# MIR50_last_version.net
KiCad netlist of a schematic drawn in EAGLE
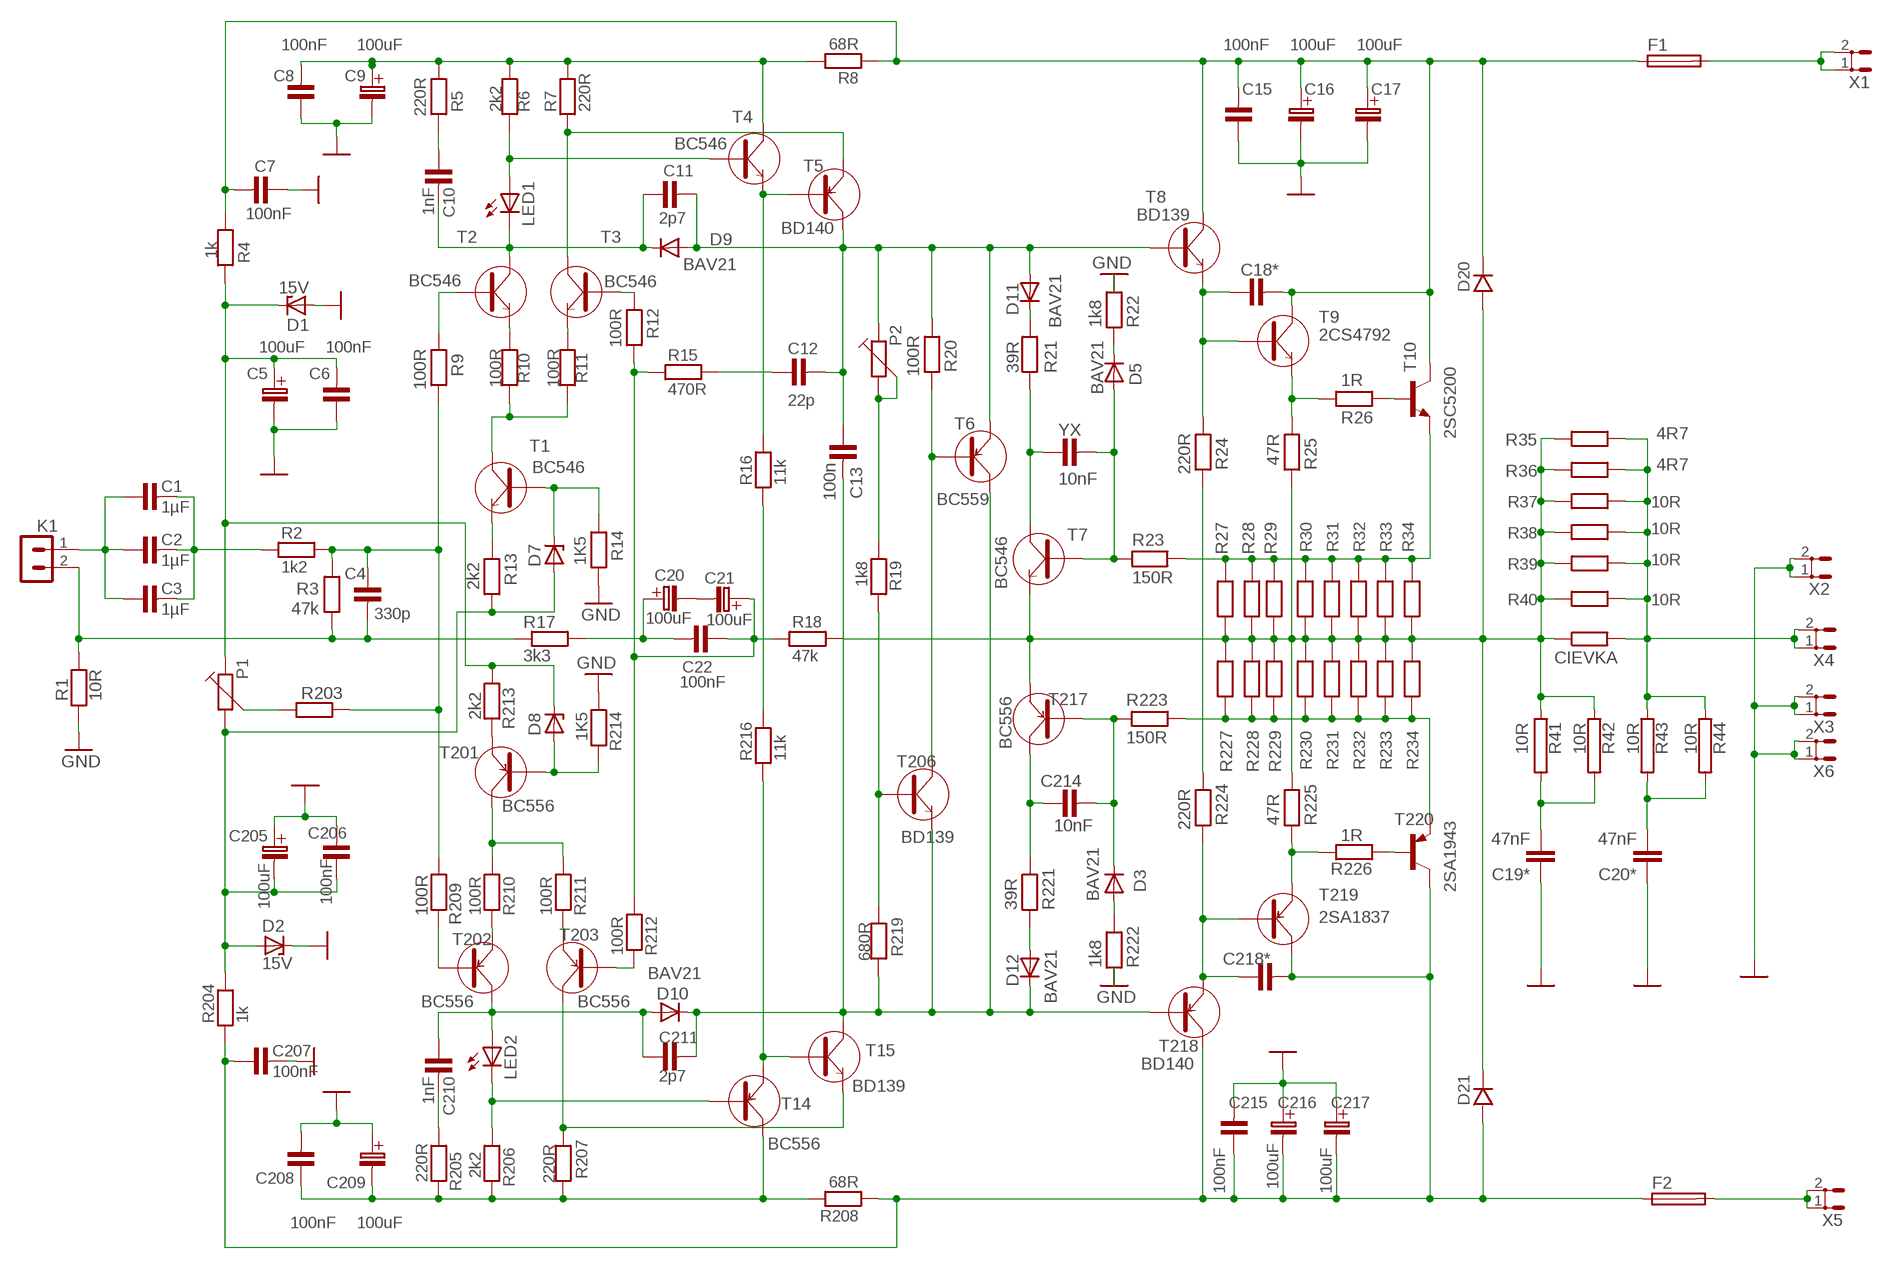
[diagram p0: schematic, sheet 1]

(export (version "E")
  (design (tool "Eeschema 10.0.6"))
  (components
    (comp (ref "C1")
      (value "1µF")
      (footprint "eagle-import:C-5")
      (libsource (lib "eagle-import") (part "C-KERAMIK_5"))
    )
    (comp (ref "C2")
      (value "1µF")
      (footprint "eagle-import:C-5")
      (libsource (lib "eagle-import") (part "C-KERAMIK_5"))
    )
    (comp (ref "C3")
      (value "1µF")
      (footprint "eagle-import:C-5")
      (libsource (lib "eagle-import") (part "C-KERAMIK_5"))
    )
    (comp (ref "C4")
      (value "330p")
      (footprint "eagle-import:C-5")
      (libsource (lib "eagle-import") (part "C-KERAMIK_5"))
    )
    (comp (ref "C5")
      (value "100uF")
      (footprint "eagle-import:C-EL_2")
      (libsource (lib "eagle-import") (part "C-ELEKTROLYT_2"))
    )
    (comp (ref "C6")
      (value "100nF")
      (footprint "eagle-import:C-5")
      (libsource (lib "eagle-import") (part "C-KERAMIK_5"))
    )
    (comp (ref "C7")
      (value "100nF")
      (footprint "eagle-import:C-5")
      (libsource (lib "eagle-import") (part "C-KERAMIK_5"))
    )
    (comp (ref "C8")
      (value "100nF")
      (footprint "eagle-import:C-5")
      (libsource (lib "eagle-import") (part "C-KERAMIK_5"))
    )
    (comp (ref "C9")
      (value "100uF")
      (footprint "eagle-import:C-EL_3,5")
      (libsource (lib "eagle-import") (part "C-ELEKTROLYT_3,5"))
    )
    (comp (ref "C10")
      (value "1nF")
      (footprint "eagle-import:C-5")
      (libsource (lib "eagle-import") (part "#PaJa_30_C-KERAMIK_5"))
    )
    (comp (ref "C11")
      (value "2p7")
      (footprint "eagle-import:C-5")
      (libsource (lib "eagle-import") (part "C-KERAMIK_5"))
    )
    (comp (ref "C12")
      (value "22p")
      (footprint "eagle-import:C-5")
      (libsource (lib "eagle-import") (part "C-KERAMIK_5"))
    )
    (comp (ref "C13")
      (value "100n")
      (footprint "eagle-import:C-5")
      (libsource (lib "eagle-import") (part "C-KERAMIK_5"))
    )
    (comp (ref "C15")
      (value "100nF")
      (footprint "eagle-import:C-5")
      (libsource (lib "eagle-import") (part "C-KERAMIK_5"))
    )
    (comp (ref "C16")
      (value "100uF")
      (footprint "eagle-import:C-EL_3,5")
      (libsource (lib "eagle-import") (part "C-ELEKTROLYT_3,5"))
    )
    (comp (ref "C17")
      (value "100uF")
      (footprint "eagle-import:C-EL_3,5")
      (libsource (lib "eagle-import") (part "C-ELEKTROLYT_3,5"))
    )
    (comp (ref "C18*")
      (value "C-KERAMIK_5")
      (footprint "eagle-import:C-5")
      (libsource (lib "eagle-import") (part "C-KERAMIK_5"))
    )
    (comp (ref "C19*")
      (value "47nF")
      (footprint "eagle-import:C150-054X183")
      (libsource (lib "eagle-import") (part "C-EU150-054X183"))
    )
    (comp (ref "C20")
      (value "100uF")
      (footprint "eagle-import:C-EL_3,5")
      (libsource (lib "eagle-import") (part "C-ELEKTROLYT_3,5"))
    )
    (comp (ref "C20*")
      (value "47nF")
      (footprint "eagle-import:C150-054X183")
      (libsource (lib "eagle-import") (part "C-EU150-054X183"))
    )
    (comp (ref "C21")
      (value "100uF")
      (footprint "eagle-import:C-EL_3,5")
      (libsource (lib "eagle-import") (part "C-ELEKTROLYT_3,5"))
    )
    (comp (ref "C22")
      (value "100nF")
      (footprint "eagle-import:C-5")
      (libsource (lib "eagle-import") (part "C-KERAMIK_5"))
    )
    (comp (ref "C205")
      (value "100uF")
      (footprint "eagle-import:C-EL_2")
      (libsource (lib "eagle-import") (part "C-ELEKTROLYT_2"))
    )
    (comp (ref "C206")
      (value "100nF")
      (footprint "eagle-import:C-5")
      (libsource (lib "eagle-import") (part "C-KERAMIK_5"))
    )
    (comp (ref "C207")
      (value "100nF")
      (footprint "eagle-import:C-5")
      (libsource (lib "eagle-import") (part "C-KERAMIK_5"))
    )
    (comp (ref "C208")
      (value "100nF")
      (footprint "eagle-import:C-5")
      (libsource (lib "eagle-import") (part "C-KERAMIK_5"))
    )
    (comp (ref "C209")
      (value "100uF")
      (footprint "eagle-import:C-EL_3,5")
      (libsource (lib "eagle-import") (part "C-ELEKTROLYT_3,5"))
    )
    (comp (ref "C210")
      (value "1nF")
      (footprint "eagle-import:C-5")
      (libsource (lib "eagle-import") (part "#PaJa_30_C-KERAMIK_5"))
    )
    (comp (ref "C211")
      (value "2p7")
      (footprint "eagle-import:C-5")
      (libsource (lib "eagle-import") (part "C-KERAMIK_5"))
    )
    (comp (ref "C214")
      (value "10nF")
      (footprint "eagle-import:C-5")
      (libsource (lib "eagle-import") (part "C-KERAMIK_5"))
    )
    (comp (ref "C215")
      (value "100nF")
      (footprint "eagle-import:C-5")
      (libsource (lib "eagle-import") (part "C-KERAMIK_5"))
    )
    (comp (ref "C216")
      (value "100uF")
      (footprint "eagle-import:C-EL_3,5")
      (libsource (lib "eagle-import") (part "C-ELEKTROLYT_3,5"))
    )
    (comp (ref "C217")
      (value "100uF")
      (footprint "eagle-import:C-EL_3,5")
      (libsource (lib "eagle-import") (part "C-ELEKTROLYT_3,5"))
    )
    (comp (ref "C218*")
      (value "C-KERAMIK_5")
      (footprint "eagle-import:C-5")
      (libsource (lib "eagle-import") (part "C-KERAMIK_5"))
    )
    (comp (ref "CIEVKA")
      (value "10R")
      (footprint "eagle-import:0617_22")
      (libsource (lib "eagle-import") (part "R-EU_0617/22"))
    )
    (comp (ref "D1")
      (value "15V")
      (footprint "eagle-import:SOD81")
      (libsource (lib "eagle-import") (part "BZD23"))
    )
    (comp (ref "D2")
      (value "15V")
      (footprint "eagle-import:SOD81")
      (libsource (lib "eagle-import") (part "BZD23"))
    )
    (comp (ref "D3")
      (value "BAV21")
      (footprint "eagle-import:DO35-10")
      (libsource (lib "eagle-import") (part "BAV21"))
    )
    (comp (ref "D5")
      (value "BAV21")
      (footprint "eagle-import:DO35-10")
      (libsource (lib "eagle-import") (part "BAV21"))
    )
    (comp (ref "D7")
      (value "BZX55")
      (footprint "eagle-import:DO35Z10")
      (libsource (lib "eagle-import") (part "BZX55"))
    )
    (comp (ref "D8")
      (value "BZX55")
      (footprint "eagle-import:DO35Z10")
      (libsource (lib "eagle-import") (part "BZX55"))
    )
    (comp (ref "D9")
      (value "BAV21")
      (footprint "eagle-import:DO35-10")
      (libsource (lib "eagle-import") (part "BAV21"))
    )
    (comp (ref "D10")
      (value "BAV21")
      (footprint "eagle-import:DO35-10")
      (libsource (lib "eagle-import") (part "BAV21"))
    )
    (comp (ref "D11")
      (value "BAV21")
      (footprint "eagle-import:DO35-10")
      (libsource (lib "eagle-import") (part "BAV21"))
    )
    (comp (ref "D12")
      (value "BAV21")
      (footprint "eagle-import:DO35-10")
      (libsource (lib "eagle-import") (part "BAV21"))
    )
    (comp (ref "D20")
      (value "D_10")
      (footprint "eagle-import:DO41")
      (libsource (lib "eagle-import") (part "D_10"))
    )
    (comp (ref "D21")
      (value "D_10")
      (footprint "eagle-import:DO41")
      (libsource (lib "eagle-import") (part "D_10"))
    )
    (comp (ref "F1")
      (value "SH22,5A")
      (footprint "eagle-import:SH22,5A")
      (libsource (lib "eagle-import") (part "SH22,5A"))
    )
    (comp (ref "F2")
      (value "SH22,5A")
      (footprint "eagle-import:SH22,5A")
      (libsource (lib "eagle-import") (part "SH22,5A"))
    )
    (comp (ref "K1")
      (value "PSH02-02P")
      (footprint "eagle-import:PSH02-02P")
      (libsource (lib "eagle-import") (part "PSH02-02P"))
    )
    (comp (ref "LED1")
      (value "LED5MM")
      (footprint "eagle-import:LED5MM")
      (libsource (lib "eagle-import") (part "LED5MM"))
    )
    (comp (ref "LED2")
      (value "LED5MM")
      (footprint "eagle-import:LED5MM")
      (libsource (lib "eagle-import") (part "LED5MM"))
    )
    (comp (ref "P1")
      (value "TRIMR64Y")
      (footprint "eagle-import:64Y")
      (libsource (lib "eagle-import") (part "TRIMR64Y"))
    )
    (comp (ref "P2")
      (value "TRIMR64Y")
      (footprint "eagle-import:64Y")
      (libsource (lib "eagle-import") (part "TRIMR64Y"))
    )
    (comp (ref "R1")
      (value "10R")
      (footprint "eagle-import:R-10")
      (libsource (lib "eagle-import") (part "#PaJa_30_R_10"))
    )
    (comp (ref "R2")
      (value "1k2")
      (footprint "eagle-import:R-10")
      (libsource (lib "eagle-import") (part "#PaJa_30_R_10"))
    )
    (comp (ref "R3")
      (value "47k")
      (footprint "eagle-import:R-10")
      (libsource (lib "eagle-import") (part "#PaJa_30_R_10"))
    )
    (comp (ref "R4")
      (value "1k")
      (footprint "eagle-import:R-10")
      (libsource (lib "eagle-import") (part "R_10"))
    )
    (comp (ref "R5")
      (value "220R")
      (footprint "eagle-import:R-10")
      (libsource (lib "eagle-import") (part "#PaJa_30_R_10"))
    )
    (comp (ref "R6")
      (value "2k2")
      (footprint "eagle-import:R-10")
      (libsource (lib "eagle-import") (part "#PaJa_30_R_10"))
    )
    (comp (ref "R7")
      (value "220R")
      (footprint "eagle-import:R-10")
      (libsource (lib "eagle-import") (part "#PaJa_30_R_10"))
    )
    (comp (ref "R8")
      (value "68R")
      (footprint "eagle-import:R-10")
      (libsource (lib "eagle-import") (part "#PaJa_30_R_10"))
    )
    (comp (ref "R9")
      (value "100R")
      (footprint "eagle-import:R-10")
      (libsource (lib "eagle-import") (part "#PaJa_30_R_10"))
    )
    (comp (ref "R10")
      (value "100R")
      (footprint "eagle-import:R-7,5")
      (libsource (lib "eagle-import") (part "R_7,5"))
    )
    (comp (ref "R11")
      (value "100R")
      (footprint "eagle-import:R-7,5")
      (libsource (lib "eagle-import") (part "R_7,5"))
    )
    (comp (ref "R12")
      (value "100R")
      (footprint "eagle-import:R-10")
      (libsource (lib "eagle-import") (part "#PaJa_30_R_10"))
    )
    (comp (ref "R13")
      (value "2k2")
      (footprint "eagle-import:R-10")
      (libsource (lib "eagle-import") (part "#PaJa_30_R_10"))
    )
    (comp (ref "R14")
      (value "1K5")
      (footprint "eagle-import:R-10")
      (libsource (lib "eagle-import") (part "#PaJa_30_R_10"))
    )
    (comp (ref "R15")
      (value "470R")
      (footprint "eagle-import:R-10")
      (libsource (lib "eagle-import") (part "R_10"))
    )
    (comp (ref "R16")
      (value "11k")
      (footprint "eagle-import:R-10")
      (libsource (lib "eagle-import") (part "R_10"))
    )
    (comp (ref "R17")
      (value "3k3")
      (footprint "eagle-import:R-10")
      (libsource (lib "eagle-import") (part "#PaJa_30_R_10"))
    )
    (comp (ref "R18")
      (value "47k")
      (footprint "eagle-import:R-10")
      (libsource (lib "eagle-import") (part "#PaJa_30_R_10"))
    )
    (comp (ref "R19")
      (value "1k8")
      (footprint "eagle-import:R-10")
      (libsource (lib "eagle-import") (part "#PaJa_30_R_10"))
    )
    (comp (ref "R20")
      (value "100R")
      (footprint "eagle-import:R-10")
      (libsource (lib "eagle-import") (part "R_10"))
    )
    (comp (ref "R21")
      (value "39R")
      (footprint "eagle-import:R-10")
      (libsource (lib "eagle-import") (part "#PaJa_30_R_10"))
    )
    (comp (ref "R22")
      (value "1k8")
      (footprint "eagle-import:R-10")
      (libsource (lib "eagle-import") (part "R_10"))
    )
    (comp (ref "R23")
      (value "150R")
      (footprint "eagle-import:R-10")
      (libsource (lib "eagle-import") (part "R_10"))
    )
    (comp (ref "R24")
      (value "220R")
      (footprint "eagle-import:R-10")
      (libsource (lib "eagle-import") (part "R_10"))
    )
    (comp (ref "R25")
      (value "47R")
      (footprint "eagle-import:R-10")
      (libsource (lib "eagle-import") (part "R_10"))
    )
    (comp (ref "R26")
      (value "1R")
      (footprint "eagle-import:R-10")
      (libsource (lib "eagle-import") (part "R_10"))
    )
    (comp (ref "R27")
      (value "R__2W")
      (footprint "eagle-import:R-_2W")
      (libsource (lib "eagle-import") (part "R__2W"))
    )
    (comp (ref "R28")
      (value "R__2W")
      (footprint "eagle-import:R-_2W")
      (libsource (lib "eagle-import") (part "R__2W"))
    )
    (comp (ref "R29")
      (value "R__2W")
      (footprint "eagle-import:R-_2W")
      (libsource (lib "eagle-import") (part "R__2W"))
    )
    (comp (ref "R30")
      (value "R_10")
      (footprint "eagle-import:R-10")
      (libsource (lib "eagle-import") (part "R_10"))
    )
    (comp (ref "R31")
      (value "R_10")
      (footprint "eagle-import:R-10")
      (libsource (lib "eagle-import") (part "R_10"))
    )
    (comp (ref "R32")
      (value "R_10")
      (footprint "eagle-import:R-10")
      (libsource (lib "eagle-import") (part "R_10"))
    )
    (comp (ref "R33")
      (value "R_10")
      (footprint "eagle-import:R-10")
      (libsource (lib "eagle-import") (part "R_10"))
    )
    (comp (ref "R34")
      (value "R_10")
      (footprint "eagle-import:R-10")
      (libsource (lib "eagle-import") (part "R_10"))
    )
    (comp (ref "R35")
      (value "4R7")
      (footprint "eagle-import:R-_2W")
      (libsource (lib "eagle-import") (part "R__2W"))
    )
    (comp (ref "R36")
      (value "4R7")
      (footprint "eagle-import:R-_2W")
      (libsource (lib "eagle-import") (part "R__2W"))
    )
    (comp (ref "R37")
      (value "10R")
      (footprint "eagle-import:R-10")
      (libsource (lib "eagle-import") (part "R_10"))
    )
    (comp (ref "R38")
      (value "10R")
      (footprint "eagle-import:R-10")
      (libsource (lib "eagle-import") (part "R_10"))
    )
    (comp (ref "R39")
      (value "10R")
      (footprint "eagle-import:R-10")
      (libsource (lib "eagle-import") (part "R_10"))
    )
    (comp (ref "R40")
      (value "10R")
      (footprint "eagle-import:R-10")
      (libsource (lib "eagle-import") (part "R_10"))
    )
    (comp (ref "R41")
      (value "10R")
      (footprint "eagle-import:AC01")
      (libsource (lib "eagle-import") (part "RAC01"))
    )
    (comp (ref "R42")
      (value "10R")
      (footprint "eagle-import:AC01")
      (libsource (lib "eagle-import") (part "RAC01"))
    )
    (comp (ref "R43")
      (value "10R")
      (footprint "eagle-import:AC01")
      (libsource (lib "eagle-import") (part "RAC01"))
    )
    (comp (ref "R44")
      (value "10R")
      (footprint "eagle-import:AC01")
      (libsource (lib "eagle-import") (part "RAC01"))
    )
    (comp (ref "R203")
      (value "R_10")
      (footprint "eagle-import:R-10")
      (libsource (lib "eagle-import") (part "#PaJa_30_R_10"))
    )
    (comp (ref "R204")
      (value "1k")
      (footprint "eagle-import:R-10")
      (libsource (lib "eagle-import") (part "R_10"))
    )
    (comp (ref "R205")
      (value "220R")
      (footprint "eagle-import:R-10")
      (libsource (lib "eagle-import") (part "#PaJa_30_R_10"))
    )
    (comp (ref "R206")
      (value "2k2")
      (footprint "eagle-import:R-10")
      (libsource (lib "eagle-import") (part "#PaJa_30_R_10"))
    )
    (comp (ref "R207")
      (value "220R")
      (footprint "eagle-import:R-10")
      (libsource (lib "eagle-import") (part "#PaJa_30_R_10"))
    )
    (comp (ref "R208")
      (value "68R")
      (footprint "eagle-import:R-10")
      (libsource (lib "eagle-import") (part "#PaJa_30_R_10"))
    )
    (comp (ref "R209")
      (value "100R")
      (footprint "eagle-import:R-10")
      (libsource (lib "eagle-import") (part "R_10"))
    )
    (comp (ref "R210")
      (value "100R")
      (footprint "eagle-import:R-7,5")
      (libsource (lib "eagle-import") (part "R_7,5"))
    )
    (comp (ref "R211")
      (value "100R")
      (footprint "eagle-import:R-7,5")
      (libsource (lib "eagle-import") (part "R_7,5"))
    )
    (comp (ref "R212")
      (value "100R")
      (footprint "eagle-import:R-10")
      (libsource (lib "eagle-import") (part "#PaJa_30_R_10"))
    )
    (comp (ref "R213")
      (value "2k2")
      (footprint "eagle-import:R-10")
      (libsource (lib "eagle-import") (part "#PaJa_30_R_10"))
    )
    (comp (ref "R214")
      (value "1K5")
      (footprint "eagle-import:R-10")
      (libsource (lib "eagle-import") (part "#PaJa_30_R_10"))
    )
    (comp (ref "R216")
      (value "11k")
      (footprint "eagle-import:R-10")
      (libsource (lib "eagle-import") (part "#PaJa_30_R_10"))
    )
    (comp (ref "R219")
      (value "680R")
      (footprint "eagle-import:R-10")
      (libsource (lib "eagle-import") (part "#PaJa_30_R_10"))
    )
    (comp (ref "R221")
      (value "39R")
      (footprint "eagle-import:R-10")
      (libsource (lib "eagle-import") (part "#PaJa_30_R_10"))
    )
    (comp (ref "R222")
      (value "1k8")
      (footprint "eagle-import:R-10")
      (libsource (lib "eagle-import") (part "R_10"))
    )
    (comp (ref "R223")
      (value "150R")
      (footprint "eagle-import:R-10")
      (libsource (lib "eagle-import") (part "R_10"))
    )
    (comp (ref "R224")
      (value "220R")
      (footprint "eagle-import:R-10")
      (libsource (lib "eagle-import") (part "R_10"))
    )
    (comp (ref "R225")
      (value "47R")
      (footprint "eagle-import:R-10")
      (libsource (lib "eagle-import") (part "R_10"))
    )
    (comp (ref "R226")
      (value "1R")
      (footprint "eagle-import:R-10")
      (libsource (lib "eagle-import") (part "R_10"))
    )
    (comp (ref "R227")
      (value "R__2W")
      (footprint "eagle-import:R-_2W")
      (libsource (lib "eagle-import") (part "R__2W"))
    )
    (comp (ref "R228")
      (value "R__2W")
      (footprint "eagle-import:R-_2W")
      (libsource (lib "eagle-import") (part "R__2W"))
    )
    (comp (ref "R229")
      (value "R__2W")
      (footprint "eagle-import:R-_2W")
      (libsource (lib "eagle-import") (part "R__2W"))
    )
    (comp (ref "R230")
      (value "R_10")
      (footprint "eagle-import:R-10")
      (libsource (lib "eagle-import") (part "R_10"))
    )
    (comp (ref "R231")
      (value "R_10")
      (footprint "eagle-import:R-10")
      (libsource (lib "eagle-import") (part "R_10"))
    )
    (comp (ref "R232")
      (value "R_10")
      (footprint "eagle-import:R-10")
      (libsource (lib "eagle-import") (part "R_10"))
    )
    (comp (ref "R233")
      (value "R_10")
      (footprint "eagle-import:R-10")
      (libsource (lib "eagle-import") (part "R_10"))
    )
    (comp (ref "R234")
      (value "R_10")
      (footprint "eagle-import:R-10")
      (libsource (lib "eagle-import") (part "R_10"))
    )
    (comp (ref "T1")
      (value "BC546")
      (footprint "eagle-import:TO-92")
      (libsource (lib "eagle-import") (part "BC546"))
    )
    (comp (ref "T2")
      (value "BC546")
      (footprint "eagle-import:TO-92")
      (libsource (lib "eagle-import") (part "BC546"))
    )
    (comp (ref "T3")
      (value "BC546")
      (footprint "eagle-import:TO-92")
      (libsource (lib "eagle-import") (part "BC546"))
    )
    (comp (ref "T4")
      (value "BC546")
      (footprint "eagle-import:TO-92")
      (libsource (lib "eagle-import") (part "BC546"))
    )
    (comp (ref "T5")
      (value "BD140")
      (footprint "eagle-import:TO-126S")
      (libsource (lib "eagle-import") (part "BD140"))
    )
    (comp (ref "T6")
      (value "BC559")
      (footprint "eagle-import:TO-92")
      (libsource (lib "eagle-import") (part "BC559"))
    )
    (comp (ref "T7")
      (value "BC546")
      (footprint "eagle-import:TO-92")
      (libsource (lib "eagle-import") (part "BC546"))
    )
    (comp (ref "T8")
      (value "BD139")
      (footprint "eagle-import:TO-126")
      (libsource (lib "eagle-import") (part "BD139_LEZ"))
    )
    (comp (ref "T9")
      (value "2CS4792")
      (footprint "eagle-import:TO-220")
      (libsource (lib "eagle-import") (part "BD711_LEZ"))
    )
    (comp (ref "T10")
      (value "2SC5200")
      (footprint "eagle-import:TO-264")
      (libsource (lib "eagle-import") (part "2SC5200"))
    )
    (comp (ref "T14")
      (value "BC556")
      (footprint "eagle-import:TO-92")
      (libsource (lib "eagle-import") (part "BC556"))
    )
    (comp (ref "T15")
      (value "BD139")
      (footprint "eagle-import:TO-126S")
      (libsource (lib "eagle-import") (part "BD139"))
    )
    (comp (ref "T201")
      (value "BC556")
      (footprint "eagle-import:TO-92")
      (libsource (lib "eagle-import") (part "BC556"))
    )
    (comp (ref "T202")
      (value "BC556")
      (footprint "eagle-import:TO-92")
      (libsource (lib "eagle-import") (part "BC556"))
    )
    (comp (ref "T203")
      (value "BC556")
      (footprint "eagle-import:TO-92")
      (libsource (lib "eagle-import") (part "BC556"))
    )
    (comp (ref "T206")
      (value "BD139")
      (footprint "eagle-import:TO-126")
      (libsource (lib "eagle-import") (part "BD139_LEZ"))
    )
    (comp (ref "T217")
      (value "BC556")
      (footprint "eagle-import:TO-92")
      (libsource (lib "eagle-import") (part "BC556"))
    )
    (comp (ref "T218")
      (value "BD140")
      (footprint "eagle-import:TO-126")
      (libsource (lib "eagle-import") (part "BD140_LEZ"))
    )
    (comp (ref "T219")
      (value "2SA1837")
      (footprint "eagle-import:TO-220")
      (libsource (lib "eagle-import") (part "BD912_LEZ"))
    )
    (comp (ref "T220")
      (value "2SA1943")
      (footprint "eagle-import:TO-264")
      (libsource (lib "eagle-import") (part "2SA1943"))
    )
    (comp (ref "X1")
      (value "ST4,8")
      (footprint "eagle-import:ST4,8")
      (libsource (lib "eagle-import") (part "ST4,8"))
    )
    (comp (ref "X2")
      (value "ST4,8")
      (footprint "eagle-import:ST4,8")
      (libsource (lib "eagle-import") (part "ST4,8"))
    )
    (comp (ref "X3")
      (value "ST4,8")
      (footprint "eagle-import:ST4,8")
      (libsource (lib "eagle-import") (part "ST4,8"))
    )
    (comp (ref "X4")
      (value "ST4,8")
      (footprint "eagle-import:ST4,8")
      (libsource (lib "eagle-import") (part "ST4,8"))
    )
    (comp (ref "X5")
      (value "ST4,8")
      (footprint "eagle-import:ST4,8")
      (libsource (lib "eagle-import") (part "ST4,8"))
    )
    (comp (ref "X6")
      (value "ST4,8")
      (footprint "eagle-import:ST4,8")
      (libsource (lib "eagle-import") (part "ST4,8"))
    )
    (comp (ref "YX")
      (value "10nF")
      (footprint "eagle-import:C-5")
      (libsource (lib "eagle-import") (part "C-KERAMIK_5"))
    )
  )
  (nets
    (net (code "1") (name "GND") (class "Default")
      (node (ref "C15") (pin "1") (pinfunction "1_1") (pintype "passive"))
      (node (ref "C16") (pin "C-") (pinfunction "C_EL-_C-") (pintype "passive"))
      (node (ref "C17") (pin "C-") (pinfunction "C_EL-_C-") (pintype "passive"))
      (node (ref "C19*") (pin "1") (pinfunction "1_1") (pintype "passive"))
      (node (ref "C20*") (pin "1") (pinfunction "1_1") (pintype "passive"))
      (node (ref "C205") (pin "C+") (pinfunction "C_EL+_C+") (pintype "passive"))
      (node (ref "C206") (pin "2") (pinfunction "2_2") (pintype "passive"))
      (node (ref "C207") (pin "2") (pinfunction "2_2") (pintype "passive"))
      (node (ref "C208") (pin "2") (pinfunction "2_2") (pintype "passive"))
      (node (ref "C209") (pin "C+") (pinfunction "C_EL+_C+") (pintype "passive"))
      (node (ref "C215") (pin "2") (pinfunction "2_2") (pintype "passive"))
      (node (ref "C216") (pin "C+") (pinfunction "C_EL+_C+") (pintype "passive"))
      (node (ref "C217") (pin "C+") (pinfunction "C_EL+_C+") (pintype "passive"))
      (node (ref "C5") (pin "C-") (pinfunction "C_EL-_C-") (pintype "passive"))
      (node (ref "C6") (pin "1") (pinfunction "1_1") (pintype "passive"))
      (node (ref "C7") (pin "1") (pinfunction "1_1") (pintype "passive"))
      (node (ref "C8") (pin "1") (pinfunction "1_1") (pintype "passive"))
      (node (ref "C9") (pin "C-") (pinfunction "C_EL-_C-") (pintype "passive"))
      (node (ref "D1") (pin "A") (pinfunction "A_A") (pintype "passive"))
      (node (ref "D2") (pin "C") (pinfunction "C_C") (pintype "passive"))
      (node (ref "R1") (pin "1") (pinfunction "1_1") (pintype "passive"))
      (node (ref "R14") (pin "1") (pinfunction "1_1") (pintype "passive"))
      (node (ref "R214") (pin "1") (pinfunction "1_1") (pintype "passive"))
      (node (ref "R22") (pin "2") (pinfunction "2_2") (pintype "passive"))
      (node (ref "R222") (pin "1") (pinfunction "1_1") (pintype "passive"))
      (node (ref "X2") (pin "1") (pinfunction "1_1") (pintype "passive"))
      (node (ref "X2") (pin "2") (pinfunction "2_2") (pintype "passive"))
      (node (ref "X3") (pin "1") (pinfunction "1_1") (pintype "passive"))
      (node (ref "X3") (pin "2") (pinfunction "2_2") (pintype "passive"))
      (node (ref "X6") (pin "1") (pinfunction "1_1") (pintype "passive"))
      (node (ref "X6") (pin "2") (pinfunction "2_2") (pintype "passive"))
    )
    (net (code "2") (name "Net-(C1-Pad1)") (class "Default")
      (node (ref "C1") (pin "1") (pinfunction "1_1") (pintype "passive"))
      (node (ref "C2") (pin "1") (pinfunction "1_1") (pintype "passive"))
      (node (ref "C3") (pin "1") (pinfunction "1_1") (pintype "passive"))
      (node (ref "K1") (pin "1") (pinfunction "1_1") (pintype "passive"))
    )
    (net (code "3") (name "Net-(C1-Pad2)") (class "Default")
      (node (ref "C1") (pin "2") (pinfunction "2_2") (pintype "passive"))
      (node (ref "C2") (pin "2") (pinfunction "2_2") (pintype "passive"))
      (node (ref "C3") (pin "2") (pinfunction "2_2") (pintype "passive"))
      (node (ref "R2") (pin "1") (pinfunction "1_1") (pintype "passive"))
    )
    (net (code "4") (name "Net-(C4-Pad1)") (class "Default")
      (node (ref "C4") (pin "1") (pinfunction "1_1") (pintype "passive"))
      (node (ref "R2") (pin "2") (pinfunction "2_2") (pintype "passive"))
      (node (ref "R203") (pin "2") (pinfunction "2_2") (pintype "passive"))
      (node (ref "R209") (pin "1") (pinfunction "1_1") (pintype "passive"))
      (node (ref "R3") (pin "2") (pinfunction "2_2") (pintype "passive"))
      (node (ref "R9") (pin "1") (pinfunction "1_1") (pintype "passive"))
    )
    (net (code "5") (name "Net-(C4-Pad2)") (class "Default")
      (node (ref "C4") (pin "2") (pinfunction "2_2") (pintype "passive"))
      (node (ref "K1") (pin "2") (pinfunction "2_2") (pintype "passive"))
      (node (ref "R1") (pin "2") (pinfunction "2_2") (pintype "passive"))
      (node (ref "R17") (pin "1") (pinfunction "1_1") (pintype "passive"))
      (node (ref "R3") (pin "1") (pinfunction "1_1") (pintype "passive"))
    )
    (net (code "6") (name "Net-(C5-C_EL+)") (class "Default")
      (node (ref "C5") (pin "C+") (pinfunction "C_EL+_C+") (pintype "passive"))
      (node (ref "C6") (pin "2") (pinfunction "2_2") (pintype "passive"))
      (node (ref "D1") (pin "C") (pinfunction "C_C") (pintype "passive"))
      (node (ref "D8") (pin "C") (pinfunction "C_C") (pintype "passive"))
      (node (ref "P1") (pin "1") (pinfunction "1_1") (pintype "passive"))
      (node (ref "R213") (pin "1") (pinfunction "1_1") (pintype "passive"))
      (node (ref "R4") (pin "1") (pinfunction "1_1") (pintype "passive"))
    )
    (net (code "7") (name "Net-(C9-C_EL+)") (class "Default")
      (node (ref "C8") (pin "2") (pinfunction "2_2") (pintype "passive"))
      (node (ref "C9") (pin "C+") (pinfunction "C_EL+_C+") (pintype "passive"))
      (node (ref "R5") (pin "2") (pinfunction "2_2") (pintype "passive"))
      (node (ref "R6") (pin "2") (pinfunction "2_2") (pintype "passive"))
      (node (ref "R7") (pin "1") (pinfunction "1_1") (pintype "passive"))
      (node (ref "R8") (pin "2") (pinfunction "2_2") (pintype "passive"))
      (node (ref "T4") (pin "1") (pinfunction "C_1") (pintype "passive"))
    )
    (net (code "8") (name "Net-(C10-Pad1)") (class "Default")
      (node (ref "C10") (pin "1") (pinfunction "1_1") (pintype "passive"))
      (node (ref "R5") (pin "1") (pinfunction "1_1") (pintype "passive"))
    )
    (net (code "9") (name "Net-(C12-Pad1)") (class "Default")
      (node (ref "C12") (pin "1") (pinfunction "1_1") (pintype "passive"))
      (node (ref "R15") (pin "2") (pinfunction "2_2") (pintype "passive"))
    )
    (net (code "10") (name "Net-(C16-C_EL+)") (class "Default")
      (node (ref "C15") (pin "2") (pinfunction "2_2") (pintype "passive"))
      (node (ref "C16") (pin "C+") (pinfunction "C_EL+_C+") (pintype "passive"))
      (node (ref "C17") (pin "C+") (pinfunction "C_EL+_C+") (pintype "passive"))
      (node (ref "C18*") (pin "2") (pinfunction "2_2") (pintype "passive"))
      (node (ref "C7") (pin "2") (pinfunction "2_2") (pintype "passive"))
      (node (ref "D20") (pin "K") (pinfunction "K_K") (pintype "passive"))
      (node (ref "F1") (pin "1") (pinfunction "1_1") (pintype "passive"))
      (node (ref "R4") (pin "2") (pinfunction "2_2") (pintype "passive"))
      (node (ref "R8") (pin "1") (pinfunction "1_1") (pintype "passive"))
      (node (ref "T10") (pin "C") (pinfunction "C_C") (pintype "passive"))
      (node (ref "T8") (pin "2") (pinfunction "C_2") (pintype "passive"))
      (node (ref "T9") (pin "2") (pinfunction "C_2") (pintype "passive"))
    )
    (net (code "11") (name "Net-(C19*-Pad2)") (class "Default")
      (node (ref "C19*") (pin "2") (pinfunction "2_2") (pintype "passive"))
      (node (ref "R41") (pin "2") (pinfunction "2_2") (pintype "passive"))
      (node (ref "R42") (pin "2") (pinfunction "2_2") (pintype "passive"))
    )
    (net (code "12") (name "Net-(C20*-Pad2)") (class "Default")
      (node (ref "C20*") (pin "2") (pinfunction "2_2") (pintype "passive"))
      (node (ref "R43") (pin "2") (pinfunction "2_2") (pintype "passive"))
      (node (ref "R44") (pin "2") (pinfunction "2_2") (pintype "passive"))
    )
    (net (code "13") (name "Net-(C20-C_EL+)") (class "Default")
      (node (ref "C20") (pin "C+") (pinfunction "C_EL+_C+") (pintype "passive"))
      (node (ref "C22") (pin "2") (pinfunction "2_2") (pintype "passive"))
      (node (ref "R17") (pin "2") (pinfunction "2_2") (pintype "passive"))
    )
    (net (code "14") (name "Net-(C20-C_EL-)") (class "Default")
      (node (ref "C20") (pin "C-") (pinfunction "C_EL-_C-") (pintype "passive"))
      (node (ref "C21") (pin "C-") (pinfunction "C_EL-_C-") (pintype "passive"))
    )
    (net (code "15") (name "Net-(C21-C_EL+)") (class "Default")
      (node (ref "C21") (pin "C+") (pinfunction "C_EL+_C+") (pintype "passive"))
      (node (ref "C22") (pin "1") (pinfunction "1_1") (pintype "passive"))
      (node (ref "R12") (pin "1") (pinfunction "1_1") (pintype "passive"))
      (node (ref "R15") (pin "1") (pinfunction "1_1") (pintype "passive"))
      (node (ref "R18") (pin "1") (pinfunction "1_1") (pintype "passive"))
      (node (ref "R212") (pin "1") (pinfunction "1_1") (pintype "passive"))
    )
    (net (code "16") (name "Net-(C205-C_EL-)") (class "Default")
      (node (ref "C205") (pin "C-") (pinfunction "C_EL-_C-") (pintype "passive"))
      (node (ref "C206") (pin "1") (pinfunction "1_1") (pintype "passive"))
      (node (ref "D2") (pin "A") (pinfunction "A_A") (pintype "passive"))
      (node (ref "D7") (pin "A") (pinfunction "A_A") (pintype "passive"))
      (node (ref "P1") (pin "2") (pinfunction "2_2") (pintype "passive"))
      (node (ref "R13") (pin "1") (pinfunction "1_1") (pintype "passive"))
      (node (ref "R204") (pin "2") (pinfunction "2_2") (pintype "passive"))
    )
    (net (code "17") (name "Net-(C209-C_EL-)") (class "Default")
      (node (ref "C208") (pin "1") (pinfunction "1_1") (pintype "passive"))
      (node (ref "C209") (pin "C-") (pinfunction "C_EL-_C-") (pintype "passive"))
      (node (ref "R205") (pin "2") (pinfunction "2_2") (pintype "passive"))
      (node (ref "R206") (pin "2") (pinfunction "2_2") (pintype "passive"))
      (node (ref "R207") (pin "1") (pinfunction "1_1") (pintype "passive"))
      (node (ref "R208") (pin "2") (pinfunction "2_2") (pintype "passive"))
      (node (ref "T14") (pin "1") (pinfunction "C_1") (pintype "passive"))
    )
    (net (code "18") (name "Net-(C210-Pad2)") (class "Default")
      (node (ref "C210") (pin "2") (pinfunction "2_2") (pintype "passive"))
      (node (ref "R205") (pin "1") (pinfunction "1_1") (pintype "passive"))
    )
    (net (code "19") (name "Net-(C216-C_EL-)") (class "Default")
      (node (ref "C207") (pin "1") (pinfunction "1_1") (pintype "passive"))
      (node (ref "C215") (pin "1") (pinfunction "1_1") (pintype "passive"))
      (node (ref "C216") (pin "C-") (pinfunction "C_EL-_C-") (pintype "passive"))
      (node (ref "C217") (pin "C-") (pinfunction "C_EL-_C-") (pintype "passive"))
      (node (ref "C218*") (pin "2") (pinfunction "2_2") (pintype "passive"))
      (node (ref "D21") (pin "A") (pinfunction "A_A") (pintype "passive"))
      (node (ref "F2") (pin "1") (pinfunction "1_1") (pintype "passive"))
      (node (ref "R204") (pin "1") (pinfunction "1_1") (pintype "passive"))
      (node (ref "R208") (pin "1") (pinfunction "1_1") (pintype "passive"))
      (node (ref "T218") (pin "2") (pinfunction "C_2") (pintype "passive"))
      (node (ref "T219") (pin "2") (pinfunction "C_2") (pintype "passive"))
      (node (ref "T220") (pin "C") (pinfunction "C_C") (pintype "passive"))
    )
    (net (code "20") (name "Net-(CIEVKA-Pad2)") (class "Default")
      (node (ref "CIEVKA") (pin "2") (pinfunction "2_2") (pintype "passive"))
      (node (ref "R35") (pin "2") (pinfunction "2_2") (pintype "passive"))
      (node (ref "R36") (pin "2") (pinfunction "2_2") (pintype "passive"))
      (node (ref "R37") (pin "1") (pinfunction "1_1") (pintype "passive"))
      (node (ref "R38") (pin "1") (pinfunction "1_1") (pintype "passive"))
      (node (ref "R39") (pin "1") (pinfunction "1_1") (pintype "passive"))
      (node (ref "R40") (pin "1") (pinfunction "1_1") (pintype "passive"))
      (node (ref "R43") (pin "1") (pinfunction "1_1") (pintype "passive"))
      (node (ref "R44") (pin "1") (pinfunction "1_1") (pintype "passive"))
      (node (ref "X4") (pin "1") (pinfunction "1_1") (pintype "passive"))
      (node (ref "X4") (pin "2") (pinfunction "2_2") (pintype "passive"))
    )
    (net (code "21") (name "Net-(D3-PadA)") (class "Default")
      (node (ref "D3") (pin "A") (pinfunction "A_A") (pintype "passive"))
      (node (ref "R222") (pin "2") (pinfunction "2_2") (pintype "passive"))
    )
    (net (code "22") (name "Net-(D5-PadC)") (class "Default")
      (node (ref "D5") (pin "C") (pinfunction "C_C") (pintype "passive"))
      (node (ref "R22") (pin "1") (pinfunction "1_1") (pintype "passive"))
    )
    (net (code "23") (name "Net-(D11-PadC)") (class "Default")
      (node (ref "D11") (pin "C") (pinfunction "C_C") (pintype "passive"))
      (node (ref "R21") (pin "1") (pinfunction "1_1") (pintype "passive"))
    )
    (net (code "24") (name "Net-(D12-PadA)") (class "Default")
      (node (ref "D12") (pin "A") (pinfunction "A_A") (pintype "passive"))
      (node (ref "R221") (pin "1") (pinfunction "1_1") (pintype "passive"))
    )
    (net (code "25") (name "Net-(F1-Pad2)") (class "Default")
      (node (ref "F1") (pin "2") (pinfunction "2_2") (pintype "passive"))
      (node (ref "X1") (pin "1") (pinfunction "1_1") (pintype "passive"))
      (node (ref "X1") (pin "2") (pinfunction "2_2") (pintype "passive"))
    )
    (net (code "26") (name "Net-(F2-Pad2)") (class "Default")
      (node (ref "F2") (pin "2") (pinfunction "2_2") (pintype "passive"))
      (node (ref "X5") (pin "1") (pinfunction "1_1") (pintype "passive"))
      (node (ref "X5") (pin "2") (pinfunction "2_2") (pintype "passive"))
    )
    (net (code "27") (name "Net-(LED1-C)") (class "Default")
      (node (ref "C10") (pin "2") (pinfunction "2_2") (pintype "passive"))
      (node (ref "C11") (pin "1") (pinfunction "1_1") (pintype "passive"))
      (node (ref "D9") (pin "C") (pinfunction "C_C") (pintype "passive"))
      (node (ref "LED1") (pin "K") (pinfunction "C_K") (pintype "passive"))
      (node (ref "T2") (pin "1") (pinfunction "C_1") (pintype "passive"))
    )
    (net (code "28") (name "Net-(LED2-C)") (class "Default")
      (node (ref "LED2") (pin "K") (pinfunction "C_K") (pintype "passive"))
      (node (ref "R206") (pin "1") (pinfunction "1_1") (pintype "passive"))
      (node (ref "T14") (pin "2") (pinfunction "B_2") (pintype "passive"))
    )
    (net (code "29") (name "Net-(P1-Pad3)") (class "Default")
      (node (ref "P1") (pin "3") (pinfunction "3_3") (pintype "passive"))
      (node (ref "R203") (pin "1") (pinfunction "1_1") (pintype "passive"))
    )
    (net (code "30") (name "Net-(P2-Pad2)") (class "Default")
      (node (ref "P2") (pin "2") (pinfunction "2_2") (pintype "passive"))
      (node (ref "P2") (pin "3") (pinfunction "3_3") (pintype "passive"))
      (node (ref "R19") (pin "1") (pinfunction "1_1") (pintype "passive"))
    )
    (net (code "31") (name "Net-(R16-Pad1)") (class "Default")
      (node (ref "R16") (pin "1") (pinfunction "1_1") (pintype "passive"))
      (node (ref "R216") (pin "2") (pinfunction "2_2") (pintype "passive"))
    )
    (net (code "32") (name "Net-(R23-Pad2)") (class "Default")
      (node (ref "R23") (pin "2") (pinfunction "2_2") (pintype "passive"))
      (node (ref "R27") (pin "2") (pinfunction "2_2") (pintype "passive"))
      (node (ref "R28") (pin "2") (pinfunction "2_2") (pintype "passive"))
      (node (ref "R29") (pin "2") (pinfunction "2_2") (pintype "passive"))
      (node (ref "R30") (pin "2") (pinfunction "2_2") (pintype "passive"))
      (node (ref "R31") (pin "2") (pinfunction "2_2") (pintype "passive"))
      (node (ref "R32") (pin "2") (pinfunction "2_2") (pintype "passive"))
      (node (ref "R33") (pin "2") (pinfunction "2_2") (pintype "passive"))
      (node (ref "R34") (pin "2") (pinfunction "2_2") (pintype "passive"))
      (node (ref "T10") (pin "E") (pinfunction "E_E") (pintype "passive"))
    )
    (net (code "33") (name "Net-(R26-Pad2)") (class "Default")
      (node (ref "R26") (pin "2") (pinfunction "2_2") (pintype "passive"))
      (node (ref "T10") (pin "B") (pinfunction "B_B") (pintype "passive"))
    )
    (net (code "34") (name "Net-(R223-Pad1)") (class "Default")
      (node (ref "R223") (pin "1") (pinfunction "1_1") (pintype "passive"))
      (node (ref "R227") (pin "1") (pinfunction "1_1") (pintype "passive"))
      (node (ref "R228") (pin "1") (pinfunction "1_1") (pintype "passive"))
      (node (ref "R229") (pin "1") (pinfunction "1_1") (pintype "passive"))
      (node (ref "R230") (pin "1") (pinfunction "1_1") (pintype "passive"))
      (node (ref "R231") (pin "1") (pinfunction "1_1") (pintype "passive"))
      (node (ref "R232") (pin "1") (pinfunction "1_1") (pintype "passive"))
      (node (ref "R233") (pin "1") (pinfunction "1_1") (pintype "passive"))
      (node (ref "R234") (pin "1") (pinfunction "1_1") (pintype "passive"))
      (node (ref "T220") (pin "E") (pinfunction "E_E") (pintype "passive"))
    )
    (net (code "35") (name "Net-(R224-Pad2)") (class "Default")
      (node (ref "R224") (pin "2") (pinfunction "2_2") (pintype "passive"))
      (node (ref "R24") (pin "1") (pinfunction "1_1") (pintype "passive"))
    )
    (net (code "36") (name "Net-(R226-Pad1)") (class "Default")
      (node (ref "R226") (pin "1") (pinfunction "1_1") (pintype "passive"))
      (node (ref "T220") (pin "B") (pinfunction "B_B") (pintype "passive"))
    )
    (net (code "37") (name "Net-(T1-B)") (class "Default")
      (node (ref "D7") (pin "C") (pinfunction "C_C") (pintype "passive"))
      (node (ref "R14") (pin "2") (pinfunction "2_2") (pintype "passive"))
      (node (ref "T1") (pin "2") (pinfunction "B_2") (pintype "passive"))
    )
    (net (code "38") (name "Net-(T1-C)") (class "Default")
      (node (ref "R10") (pin "1") (pinfunction "1_1") (pintype "passive"))
      (node (ref "R11") (pin "1") (pinfunction "1_1") (pintype "passive"))
      (node (ref "T1") (pin "1") (pinfunction "C_1") (pintype "passive"))
    )
    (net (code "39") (name "Net-(T1-E)") (class "Default")
      (node (ref "R13") (pin "2") (pinfunction "2_2") (pintype "passive"))
      (node (ref "T1") (pin "3") (pinfunction "E_3") (pintype "passive"))
    )
    (net (code "40") (name "Net-(T2-B)") (class "Default")
      (node (ref "R9") (pin "2") (pinfunction "2_2") (pintype "passive"))
      (node (ref "T2") (pin "2") (pinfunction "B_2") (pintype "passive"))
    )
    (net (code "41") (name "Net-(T2-E)") (class "Default")
      (node (ref "R10") (pin "2") (pinfunction "2_2") (pintype "passive"))
      (node (ref "T2") (pin "3") (pinfunction "E_3") (pintype "passive"))
    )
    (net (code "42") (name "Net-(T3-B)") (class "Default")
      (node (ref "R12") (pin "2") (pinfunction "2_2") (pintype "passive"))
      (node (ref "T3") (pin "2") (pinfunction "B_2") (pintype "passive"))
    )
    (net (code "43") (name "Net-(T3-C)") (class "Default")
      (node (ref "R7") (pin "2") (pinfunction "2_2") (pintype "passive"))
      (node (ref "T3") (pin "1") (pinfunction "C_1") (pintype "passive"))
      (node (ref "T5") (pin "1") (pinfunction "E_1") (pintype "passive"))
    )
    (net (code "44") (name "Net-(T3-E)") (class "Default")
      (node (ref "R11") (pin "2") (pinfunction "2_2") (pintype "passive"))
      (node (ref "T3") (pin "3") (pinfunction "E_3") (pintype "passive"))
    )
    (net (code "45") (name "Net-(T4-B)") (class "Default")
      (node (ref "LED1") (pin "A") (pinfunction "A_A") (pintype "passive"))
      (node (ref "R6") (pin "1") (pinfunction "1_1") (pintype "passive"))
      (node (ref "T4") (pin "2") (pinfunction "B_2") (pintype "passive"))
    )
    (net (code "46") (name "Net-(T4-E)") (class "Default")
      (node (ref "R16") (pin "2") (pinfunction "2_2") (pintype "passive"))
      (node (ref "T4") (pin "3") (pinfunction "E_3") (pintype "passive"))
      (node (ref "T5") (pin "3") (pinfunction "B_3") (pintype "passive"))
    )
    (net (code "47") (name "Net-(T5-C)") (class "Default")
      (node (ref "C11") (pin "2") (pinfunction "2_2") (pintype "passive"))
      (node (ref "C12") (pin "2") (pinfunction "2_2") (pintype "passive"))
      (node (ref "C13") (pin "1") (pinfunction "1_1") (pintype "passive"))
      (node (ref "D11") (pin "A") (pinfunction "A_A") (pintype "passive"))
      (node (ref "D9") (pin "A") (pinfunction "A_A") (pintype "passive"))
      (node (ref "P2") (pin "1") (pinfunction "1_1") (pintype "passive"))
      (node (ref "R20") (pin "2") (pinfunction "2_2") (pintype "passive"))
      (node (ref "T5") (pin "2") (pinfunction "C_2") (pintype "passive"))
      (node (ref "T6") (pin "3") (pinfunction "E_3") (pintype "passive"))
      (node (ref "T8") (pin "3") (pinfunction "B_3") (pintype "passive"))
    )
    (net (code "48") (name "Net-(T7-B)") (class "Default")
      (node (ref "D5") (pin "A") (pinfunction "A_A") (pintype "passive"))
      (node (ref "R23") (pin "1") (pinfunction "1_1") (pintype "passive"))
      (node (ref "T7") (pin "2") (pinfunction "B_2") (pintype "passive"))
      (node (ref "YX") (pin "2") (pinfunction "2_2") (pintype "passive"))
    )
    (net (code "49") (name "Net-(T7-C)") (class "Default")
      (node (ref "R21") (pin "2") (pinfunction "2_2") (pintype "passive"))
      (node (ref "T7") (pin "1") (pinfunction "C_1") (pintype "passive"))
      (node (ref "YX") (pin "1") (pinfunction "1_1") (pintype "passive"))
    )
    (net (code "50") (name "Net-(T8-E)") (class "Default")
      (node (ref "C18*") (pin "1") (pinfunction "1_1") (pintype "passive"))
      (node (ref "R24") (pin "2") (pinfunction "2_2") (pintype "passive"))
      (node (ref "T8") (pin "1") (pinfunction "E_1") (pintype "passive"))
      (node (ref "T9") (pin "1") (pinfunction "B_1") (pintype "passive"))
    )
    (net (code "51") (name "Net-(T9-E)") (class "Default")
      (node (ref "R25") (pin "2") (pinfunction "2_2") (pintype "passive"))
      (node (ref "R26") (pin "1") (pinfunction "1_1") (pintype "passive"))
      (node (ref "T9") (pin "3") (pinfunction "E_3") (pintype "passive"))
    )
    (net (code "52") (name "Net-(T14-E)") (class "Default")
      (node (ref "R216") (pin "1") (pinfunction "1_1") (pintype "passive"))
      (node (ref "T14") (pin "3") (pinfunction "E_3") (pintype "passive"))
      (node (ref "T15") (pin "3") (pinfunction "B_3") (pintype "passive"))
    )
    (net (code "53") (name "Net-(T15-C)") (class "Default")
      (node (ref "C13") (pin "2") (pinfunction "2_2") (pintype "passive"))
      (node (ref "C211") (pin "2") (pinfunction "2_2") (pintype "passive"))
      (node (ref "D10") (pin "C") (pinfunction "C_C") (pintype "passive"))
      (node (ref "D12") (pin "C") (pinfunction "C_C") (pintype "passive"))
      (node (ref "R219") (pin "1") (pinfunction "1_1") (pintype "passive"))
      (node (ref "T15") (pin "2") (pinfunction "C_2") (pintype "passive"))
      (node (ref "T206") (pin "1") (pinfunction "E_1") (pintype "passive"))
      (node (ref "T218") (pin "3") (pinfunction "B_3") (pintype "passive"))
      (node (ref "T6") (pin "1") (pinfunction "C_1") (pintype "passive"))
    )
    (net (code "54") (name "Net-(T15-E)") (class "Default")
      (node (ref "R207") (pin "2") (pinfunction "2_2") (pintype "passive"))
      (node (ref "T15") (pin "1") (pinfunction "E_1") (pintype "passive"))
      (node (ref "T203") (pin "1") (pinfunction "C_1") (pintype "passive"))
    )
    (net (code "55") (name "Net-(T201-B)") (class "Default")
      (node (ref "D8") (pin "A") (pinfunction "A_A") (pintype "passive"))
      (node (ref "R214") (pin "2") (pinfunction "2_2") (pintype "passive"))
      (node (ref "T201") (pin "2") (pinfunction "B_2") (pintype "passive"))
    )
    (net (code "56") (name "Net-(T201-C)") (class "Default")
      (node (ref "R210") (pin "1") (pinfunction "1_1") (pintype "passive"))
      (node (ref "R211") (pin "1") (pinfunction "1_1") (pintype "passive"))
      (node (ref "T201") (pin "1") (pinfunction "C_1") (pintype "passive"))
    )
    (net (code "57") (name "Net-(T201-E)") (class "Default")
      (node (ref "R213") (pin "2") (pinfunction "2_2") (pintype "passive"))
      (node (ref "T201") (pin "3") (pinfunction "E_3") (pintype "passive"))
    )
    (net (code "58") (name "Net-(T202-B)") (class "Default")
      (node (ref "R209") (pin "2") (pinfunction "2_2") (pintype "passive"))
      (node (ref "T202") (pin "2") (pinfunction "B_2") (pintype "passive"))
    )
    (net (code "59") (name "Net-(T202-C)") (class "Default")
      (node (ref "C210") (pin "1") (pinfunction "1_1") (pintype "passive"))
      (node (ref "C211") (pin "1") (pinfunction "1_1") (pintype "passive"))
      (node (ref "D10") (pin "A") (pinfunction "A_A") (pintype "passive"))
      (node (ref "LED2") (pin "A") (pinfunction "A_A") (pintype "passive"))
      (node (ref "T202") (pin "1") (pinfunction "C_1") (pintype "passive"))
    )
    (net (code "60") (name "Net-(T202-E)") (class "Default")
      (node (ref "R210") (pin "2") (pinfunction "2_2") (pintype "passive"))
      (node (ref "T202") (pin "3") (pinfunction "E_3") (pintype "passive"))
    )
    (net (code "61") (name "Net-(T203-B)") (class "Default")
      (node (ref "R212") (pin "2") (pinfunction "2_2") (pintype "passive"))
      (node (ref "T203") (pin "2") (pinfunction "B_2") (pintype "passive"))
    )
    (net (code "62") (name "Net-(T203-E)") (class "Default")
      (node (ref "R211") (pin "2") (pinfunction "2_2") (pintype "passive"))
      (node (ref "T203") (pin "3") (pinfunction "E_3") (pintype "passive"))
    )
    (net (code "63") (name "Net-(T206-B)") (class "Default")
      (node (ref "R19") (pin "2") (pinfunction "2_2") (pintype "passive"))
      (node (ref "R219") (pin "2") (pinfunction "2_2") (pintype "passive"))
      (node (ref "T206") (pin "3") (pinfunction "B_3") (pintype "passive"))
    )
    (net (code "64") (name "Net-(T206-C)") (class "Default")
      (node (ref "R20") (pin "1") (pinfunction "1_1") (pintype "passive"))
      (node (ref "T206") (pin "2") (pinfunction "C_2") (pintype "passive"))
      (node (ref "T6") (pin "2") (pinfunction "B_2") (pintype "passive"))
    )
    (net (code "65") (name "Net-(T217-B)") (class "Default")
      (node (ref "C214") (pin "2") (pinfunction "2_2") (pintype "passive"))
      (node (ref "D3") (pin "C") (pinfunction "C_C") (pintype "passive"))
      (node (ref "R223") (pin "2") (pinfunction "2_2") (pintype "passive"))
      (node (ref "T217") (pin "2") (pinfunction "B_2") (pintype "passive"))
    )
    (net (code "66") (name "Net-(T217-C)") (class "Default")
      (node (ref "C214") (pin "1") (pinfunction "1_1") (pintype "passive"))
      (node (ref "R221") (pin "2") (pinfunction "2_2") (pintype "passive"))
      (node (ref "T217") (pin "1") (pinfunction "C_1") (pintype "passive"))
    )
    (net (code "67") (name "Net-(T217-E)") (class "Default")
      (node (ref "CIEVKA") (pin "1") (pinfunction "1_1") (pintype "passive"))
      (node (ref "D20") (pin "A") (pinfunction "A_A") (pintype "passive"))
      (node (ref "D21") (pin "K") (pinfunction "K_K") (pintype "passive"))
      (node (ref "R18") (pin "2") (pinfunction "2_2") (pintype "passive"))
      (node (ref "R225") (pin "2") (pinfunction "2_2") (pintype "passive"))
      (node (ref "R227") (pin "2") (pinfunction "2_2") (pintype "passive"))
      (node (ref "R228") (pin "2") (pinfunction "2_2") (pintype "passive"))
      (node (ref "R229") (pin "2") (pinfunction "2_2") (pintype "passive"))
      (node (ref "R230") (pin "2") (pinfunction "2_2") (pintype "passive"))
      (node (ref "R231") (pin "2") (pinfunction "2_2") (pintype "passive"))
      (node (ref "R232") (pin "2") (pinfunction "2_2") (pintype "passive"))
      (node (ref "R233") (pin "2") (pinfunction "2_2") (pintype "passive"))
      (node (ref "R234") (pin "2") (pinfunction "2_2") (pintype "passive"))
      (node (ref "R25") (pin "1") (pinfunction "1_1") (pintype "passive"))
      (node (ref "R27") (pin "1") (pinfunction "1_1") (pintype "passive"))
      (node (ref "R28") (pin "1") (pinfunction "1_1") (pintype "passive"))
      (node (ref "R29") (pin "1") (pinfunction "1_1") (pintype "passive"))
      (node (ref "R30") (pin "1") (pinfunction "1_1") (pintype "passive"))
      (node (ref "R31") (pin "1") (pinfunction "1_1") (pintype "passive"))
      (node (ref "R32") (pin "1") (pinfunction "1_1") (pintype "passive"))
      (node (ref "R33") (pin "1") (pinfunction "1_1") (pintype "passive"))
      (node (ref "R34") (pin "1") (pinfunction "1_1") (pintype "passive"))
      (node (ref "R35") (pin "1") (pinfunction "1_1") (pintype "passive"))
      (node (ref "R36") (pin "1") (pinfunction "1_1") (pintype "passive"))
      (node (ref "R37") (pin "2") (pinfunction "2_2") (pintype "passive"))
      (node (ref "R38") (pin "2") (pinfunction "2_2") (pintype "passive"))
      (node (ref "R39") (pin "2") (pinfunction "2_2") (pintype "passive"))
      (node (ref "R40") (pin "2") (pinfunction "2_2") (pintype "passive"))
      (node (ref "R41") (pin "1") (pinfunction "1_1") (pintype "passive"))
      (node (ref "R42") (pin "1") (pinfunction "1_1") (pintype "passive"))
      (node (ref "T217") (pin "3") (pinfunction "E_3") (pintype "passive"))
      (node (ref "T7") (pin "3") (pinfunction "E_3") (pintype "passive"))
    )
    (net (code "68") (name "Net-(T218-E)") (class "Default")
      (node (ref "C218*") (pin "1") (pinfunction "1_1") (pintype "passive"))
      (node (ref "R224") (pin "1") (pinfunction "1_1") (pintype "passive"))
      (node (ref "T218") (pin "1") (pinfunction "E_1") (pintype "passive"))
      (node (ref "T219") (pin "1") (pinfunction "B_1") (pintype "passive"))
    )
    (net (code "69") (name "Net-(T219-E)") (class "Default")
      (node (ref "R225") (pin "1") (pinfunction "1_1") (pintype "passive"))
      (node (ref "R226") (pin "2") (pinfunction "2_2") (pintype "passive"))
      (node (ref "T219") (pin "3") (pinfunction "E_3") (pintype "passive"))
    )
  )
)
